# CONTROL_AND_COMMUNICATION.net
KiCad netlist of a schematic drawn in Altium Designer
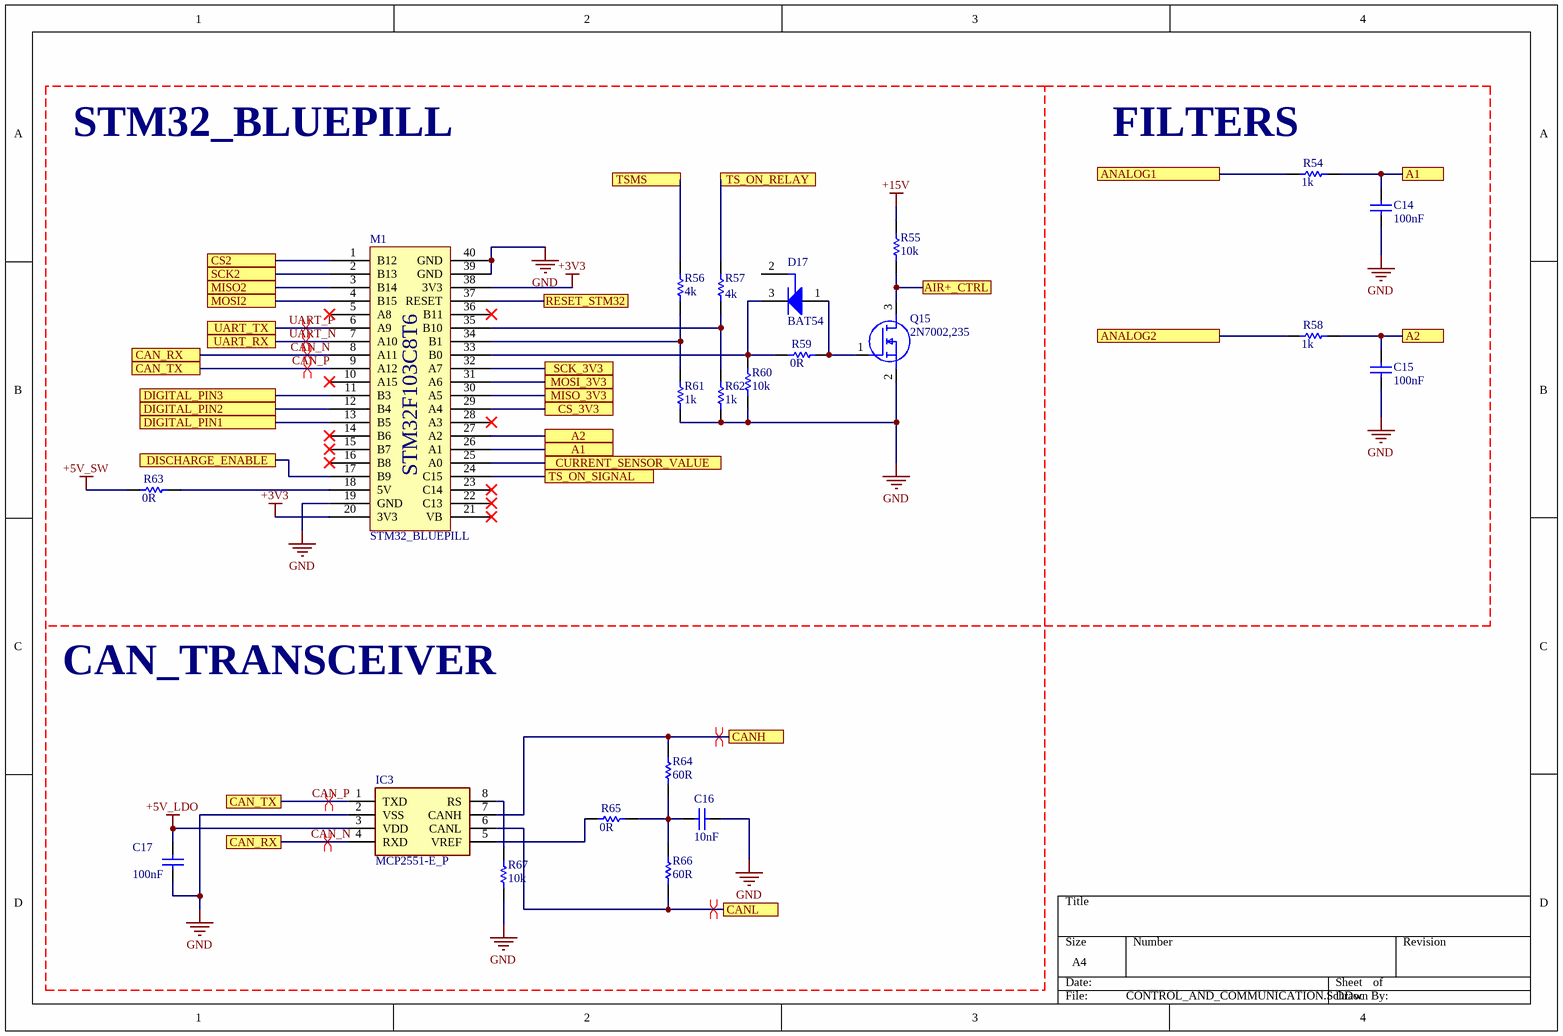
[diagram p0: CONTROL_AND_COMMUNICATION.SchDoc]

(export (version "E")
  (design (tool "Eeschema 10.0.6"))
  (components
    (comp (ref "C14")
      (value "100nF")
      (footprint "KEMT-1206-2_N")
      (description "CAP, Ceramic, 0.1 uF, +/- 10%, 50 V, -55 to 125 degC, 1206 (3216 Metric), RoHS, Tape and Reel")
      (fields (field (name "MANUFACTURER") "Kemet"))
      (libsource (lib "Schlib1_TSAL_LV_3.1") (part "CMP-1037-04202-2"))
    )
    (comp (ref "C15")
      (value "100nF")
      (footprint "KEMT-1206-2_N")
      (description "CAP, Ceramic, 0.1 uF, +/- 10%, 50 V, -55 to 125 degC, 1206 (3216 Metric), RoHS, Tape and Reel")
      (fields (field (name "MANUFACTURER") "Kemet"))
      (libsource (lib "Schlib1_TSAL_LV_3.1") (part "CMP-1037-04202-2"))
    )
    (comp (ref "C16")
      (value "10nF")
      (footprint "KEMT-1206-2_N")
      (description "CAP, Ceramic, 0.1 uF, +/- 10%, 50 V, -55 to 125 degC, 1206 (3216 Metric), RoHS, Tape and Reel")
      (fields (field (name "MANUFACTURER") "Kemet"))
      (libsource (lib "Schlib1_TSAL_LV_3.1") (part "CMP-1037-04202-2"))
    )
    (comp (ref "C17")
      (value "100nF")
      (footprint "KEMT-1206-2_N")
      (description "CAP, Ceramic, 0.1 uF, +/- 10%, 50 V, -55 to 125 degC, 1206 (3216 Metric), RoHS, Tape and Reel")
      (fields (field (name "MANUFACTURER") "Kemet"))
      (libsource (lib "Schlib1_TSAL_LV_3.1") (part "CMP-1037-04202-2"))
    )
    (comp (ref "D17")
      (value "BAT54")
      (footprint "INF-SOT23_N")
      (description "Silicon Schottky Diode, SOT23, Reel, Green")
      (fields (field (name "MANUFACTURER") "Infineon"))
      (libsource (lib "Schlib1") (part "CMP-1182-00010-1"))
    )
    (comp (ref "IC3")
      (value "MCP2551-E_P")
      (footprint "SamacSys:DIP794W56P254L946H432Q8N")
      (description "Integrated Circuit")
      (fields
        (field (name "MANUFACTURER_PART_NUMBER") "MCP2551-E/P")
        (field (name "MOUSER PART NUMBER") "579-MCP2551-E/P")
      )
      (libsource (lib "*") (part "MCP2551-E_P"))
    )
    (comp (ref "M1")
      (value "STM32_BLUEPILL")
      (footprint "stm32_bluepill")
      (libsource (lib "Regular_used_components_2D_Symbol") (part "stm32_bluepill"))
    )
    (comp (ref "Q15")
      (value "2N7002,235")
      (footprint "SamacSys:SOT95P230X110-3N")
      (description "MOSFET (N-Channel)")
      (fields (field (name "MOUSER PART NUMBER") "771-2N7002235"))
      (libsource (lib "*") (part "2N7002,235"))
    )
    (comp (ref "R54")
      (value "1k")
      (footprint "RESC3216X60X45NL10T20 - duplicate")
      (fields (field (name "PART NUMBER") "CRCW120647K0FKEA") (field (name "MANUFACTURER") "Vishay Dale"))
      (libsource (lib "Regular_used_components_2D_Symbol") (part "CMP-2003-02213-1"))
    )
    (comp (ref "R55")
      (value "10k")
      (footprint "RESC3216X60X45NL10T20 - duplicate")
      (fields (field (name "PART NUMBER") "CRCW120647K0FKEA") (field (name "MANUFACTURER") "Vishay Dale"))
      (libsource (lib "Regular_used_components_2D_Symbol") (part "CMP-2003-02213-1"))
    )
    (comp (ref "R56")
      (value "4k")
      (footprint "RESC3216X60X45NL10T20 - duplicate")
      (fields (field (name "PART NUMBER") "CRCW120647K0FKEA") (field (name "MANUFACTURER") "Vishay Dale"))
      (libsource (lib "Regular_used_components_2D_Symbol") (part "CMP-2003-02213-1"))
    )
    (comp (ref "R57")
      (value "4k")
      (footprint "RESC3216X60X45NL10T20 - duplicate")
      (fields (field (name "PART NUMBER") "CRCW120647K0FKEA") (field (name "MANUFACTURER") "Vishay Dale"))
      (libsource (lib "Regular_used_components_2D_Symbol") (part "CMP-2003-02213-1"))
    )
    (comp (ref "R58")
      (value "1k")
      (footprint "RESC3216X60X45NL10T20 - duplicate")
      (fields (field (name "PART NUMBER") "CRCW120647K0FKEA") (field (name "MANUFACTURER") "Vishay Dale"))
      (libsource (lib "Regular_used_components_2D_Symbol") (part "CMP-2003-02213-1"))
    )
    (comp (ref "R59")
      (value "0R")
      (footprint "RESC3216X60X45NL10T20 - duplicate")
      (fields (field (name "PART NUMBER") "CRCW120647K0FKEA") (field (name "MANUFACTURER") "Vishay Dale"))
      (libsource (lib "Regular_used_components_2D_Symbol") (part "CMP-2003-02213-1"))
    )
    (comp (ref "R60")
      (value "10k")
      (footprint "RESC3216X60X45NL10T20 - duplicate")
      (fields (field (name "PART NUMBER") "CRCW120647K0FKEA") (field (name "MANUFACTURER") "Vishay Dale"))
      (libsource (lib "Regular_used_components_2D_Symbol") (part "CMP-2003-02213-1"))
    )
    (comp (ref "R61")
      (value "1k")
      (footprint "RESC3216X60X45NL10T20 - duplicate")
      (fields (field (name "PART NUMBER") "CRCW120647K0FKEA") (field (name "MANUFACTURER") "Vishay Dale"))
      (libsource (lib "Regular_used_components_2D_Symbol") (part "CMP-2003-02213-1"))
    )
    (comp (ref "R62")
      (value "1k")
      (footprint "RESC3216X60X45NL10T20 - duplicate")
      (fields (field (name "PART NUMBER") "CRCW120647K0FKEA") (field (name "MANUFACTURER") "Vishay Dale"))
      (libsource (lib "Regular_used_components_2D_Symbol") (part "CMP-2003-02213-1"))
    )
    (comp (ref "R63")
      (value "0R")
      (footprint "RESC3216X60X45NL10T20 - duplicate")
      (fields (field (name "PART NUMBER") "CRCW120647K0FKEA") (field (name "MANUFACTURER") "Vishay Dale"))
      (libsource (lib "Regular_used_components_2D_Symbol") (part "CMP-2003-02213-1"))
    )
    (comp (ref "R64")
      (value "60R")
      (footprint "RESC3216X60X45NL10T20 - duplicate")
      (fields (field (name "PART NUMBER") "CRCW120647K0FKEA") (field (name "MANUFACTURER") "Vishay Dale"))
      (libsource (lib "Regular_used_components_2D_Symbol") (part "CMP-2003-02213-1"))
    )
    (comp (ref "R65")
      (value "0R")
      (footprint "RESC3216X60X45NL10T20 - duplicate")
      (fields (field (name "PART NUMBER") "CRCW120647K0FKEA") (field (name "MANUFACTURER") "Vishay Dale"))
      (libsource (lib "Regular_used_components_2D_Symbol") (part "CMP-2003-02213-1"))
    )
    (comp (ref "R66")
      (value "60R")
      (footprint "RESC3216X60X45NL10T20 - duplicate")
      (fields (field (name "PART NUMBER") "CRCW120647K0FKEA") (field (name "MANUFACTURER") "Vishay Dale"))
      (libsource (lib "Regular_used_components_2D_Symbol") (part "CMP-2003-02213-1"))
    )
    (comp (ref "R67")
      (value "10k")
      (footprint "RESC3216X60X45NL10T20 - duplicate")
      (fields (field (name "PART NUMBER") "CRCW120647K0FKEA") (field (name "MANUFACTURER") "Vishay Dale"))
      (libsource (lib "Regular_used_components_2D_Symbol") (part "CMP-2003-02213-1"))
    )
  )
  (nets
    (net (code "1") (name "+3V3") (class "Default")
      (node (ref "M1") (pin "20") (pinfunction "3V3_20") (pintype "passive"))
      (node (ref "M1") (pin "38") (pinfunction "3V3_38") (pintype "passive"))
    )
    (net (code "2") (name "+5V_LDO") (class "Default")
      (node (ref "C17") (pin "1") (pinfunction "1_1") (pintype "passive"))
      (node (ref "IC3") (pin "3") (pinfunction "VDD_3") (pintype "passive"))
    )
    (net (code "3") (name "+5V_SW") (class "Default")
      (node (ref "R63") (pin "2") (pinfunction "2_2") (pintype "passive"))
    )
    (net (code "4") (name "+15V") (class "Default")
      (node (ref "R55") (pin "1") (pinfunction "1_1") (pintype "passive"))
    )
    (net (code "5") (name "/A1") (class "Default")
      (node (ref "C14") (pin "1") (pinfunction "1_1") (pintype "passive"))
      (node (ref "M1") (pin "26") (pinfunction "A1_26") (pintype "passive"))
      (node (ref "R54") (pin "1") (pinfunction "1_1") (pintype "passive"))
    )
    (net (code "6") (name "/A2") (class "Default")
      (node (ref "C15") (pin "1") (pinfunction "1_1") (pintype "passive"))
      (node (ref "M1") (pin "27") (pinfunction "A2_27") (pintype "passive"))
      (node (ref "R58") (pin "1") (pinfunction "1_1") (pintype "passive"))
    )
    (net (code "7") (name "/AIR+_CTRL") (class "Default")
      (node (ref "Q15") (pin "3") (pinfunction "D_3") (pintype "passive"))
      (node (ref "R55") (pin "2") (pinfunction "2_2") (pintype "passive"))
    )
    (net (code "8") (name "/ANALOG1") (class "Default")
      (node (ref "R54") (pin "2") (pinfunction "2_2") (pintype "passive"))
    )
    (net (code "9") (name "/ANALOG2") (class "Default")
      (node (ref "R58") (pin "2") (pinfunction "2_2") (pintype "passive"))
    )
    (net (code "10") (name "/CANH") (class "Default")
      (node (ref "IC3") (pin "7") (pinfunction "CANH_7") (pintype "passive"))
      (node (ref "R64") (pin "2") (pinfunction "2_2") (pintype "passive"))
    )
    (net (code "11") (name "/CANL") (class "Default")
      (node (ref "IC3") (pin "6") (pinfunction "CANL_6") (pintype "passive"))
      (node (ref "R66") (pin "2") (pinfunction "2_2") (pintype "passive"))
    )
    (net (code "12") (name "/CAN_N") (class "Default")
      (node (ref "IC3") (pin "4") (pinfunction "RXD_4") (pintype "passive"))
      (node (ref "M1") (pin "8") (pinfunction "A11_8") (pintype "passive"))
    )
    (net (code "13") (name "/CAN_P") (class "Default")
      (node (ref "IC3") (pin "1") (pinfunction "TXD_1") (pintype "passive"))
      (node (ref "M1") (pin "9") (pinfunction "A12_9") (pintype "passive"))
    )
    (net (code "14") (name "/CS2") (class "Default")
      (node (ref "M1") (pin "1") (pinfunction "B12_1") (pintype "passive"))
    )
    (net (code "15") (name "/CS_3V3") (class "Default")
      (node (ref "M1") (pin "29") (pinfunction "A4_29") (pintype "passive"))
    )
    (net (code "16") (name "/CURRENT_SENSOR_VALUE") (class "Default")
      (node (ref "M1") (pin "25") (pinfunction "A0_25") (pintype "passive"))
    )
    (net (code "17") (name "/DIGITAL_PIN1") (class "Default")
      (node (ref "M1") (pin "13") (pinfunction "B5_13") (pintype "passive"))
    )
    (net (code "18") (name "/DIGITAL_PIN2") (class "Default")
      (node (ref "M1") (pin "12") (pinfunction "B4_12") (pintype "passive"))
    )
    (net (code "19") (name "/DIGITAL_PIN3") (class "Default")
      (node (ref "M1") (pin "11") (pinfunction "B3_11") (pintype "passive"))
    )
    (net (code "20") (name "/DISCHARGE_ENABLE") (class "Default")
      (node (ref "M1") (pin "17") (pinfunction "B9_17") (pintype "passive"))
    )
    (net (code "21") (name "/MISO2") (class "Default")
      (node (ref "M1") (pin "3") (pinfunction "B14_3") (pintype "passive"))
    )
    (net (code "22") (name "/MISO_3V3") (class "Default")
      (node (ref "M1") (pin "30") (pinfunction "A5_30") (pintype "passive"))
    )
    (net (code "23") (name "/MOSI2") (class "Default")
      (node (ref "M1") (pin "4") (pinfunction "B15_4") (pintype "passive"))
    )
    (net (code "24") (name "/MOSI_3V3") (class "Default")
      (node (ref "M1") (pin "31") (pinfunction "A6_31") (pintype "passive"))
    )
    (net (code "25") (name "/RESET_STM32") (class "Default")
      (node (ref "M1") (pin "37") (pinfunction "RESET_37") (pintype "passive"))
    )
    (net (code "26") (name "/SCK2") (class "Default")
      (node (ref "M1") (pin "2") (pinfunction "B13_2") (pintype "passive"))
    )
    (net (code "27") (name "/SCK_3V3") (class "Default")
      (node (ref "M1") (pin "32") (pinfunction "A7_32") (pintype "passive"))
    )
    (net (code "28") (name "/TSMS") (class "Default")
      (node (ref "R56") (pin "1") (pinfunction "1_1") (pintype "passive"))
    )
    (net (code "29") (name "/TS_ON_RELAY") (class "Default")
      (node (ref "R57") (pin "1") (pinfunction "1_1") (pintype "passive"))
    )
    (net (code "30") (name "/TS_ON_SIGNAL") (class "Default")
      (node (ref "M1") (pin "24") (pinfunction "C15_24") (pintype "passive"))
    )
    (net (code "31") (name "/UART_N") (class "Default")
      (node (ref "M1") (pin "7") (pinfunction "A10_7") (pintype "passive"))
    )
    (net (code "32") (name "/UART_P") (class "Default")
      (node (ref "M1") (pin "6") (pinfunction "A9_6") (pintype "passive"))
    )
    (net (code "33") (name "GND") (class "Default")
      (node (ref "C14") (pin "2") (pinfunction "2_2") (pintype "passive"))
      (node (ref "C15") (pin "2") (pinfunction "2_2") (pintype "passive"))
      (node (ref "C16") (pin "2") (pinfunction "2_2") (pintype "passive"))
      (node (ref "C17") (pin "2") (pinfunction "2_2") (pintype "passive"))
      (node (ref "IC3") (pin "2") (pinfunction "VSS_2") (pintype "passive"))
      (node (ref "M1") (pin "19") (pinfunction "GND_19") (pintype "passive"))
      (node (ref "M1") (pin "39") (pinfunction "GND_39") (pintype "passive"))
      (node (ref "M1") (pin "40") (pinfunction "GND_40") (pintype "passive"))
      (node (ref "Q15") (pin "2") (pinfunction "S_2") (pintype "passive"))
      (node (ref "R60") (pin "2") (pinfunction "2_2") (pintype "passive"))
      (node (ref "R61") (pin "2") (pinfunction "2_2") (pintype "passive"))
      (node (ref "R62") (pin "2") (pinfunction "2_2") (pintype "passive"))
      (node (ref "R67") (pin "2") (pinfunction "2_2") (pintype "passive"))
    )
    (net (code "34") (name "Net-(C16-Pad1)") (class "Default")
      (node (ref "C16") (pin "1") (pinfunction "1_1") (pintype "passive"))
      (node (ref "R64") (pin "1") (pinfunction "1_1") (pintype "passive"))
      (node (ref "R65") (pin "1") (pinfunction "1_1") (pintype "passive"))
      (node (ref "R66") (pin "1") (pinfunction "1_1") (pintype "passive"))
    )
    (net (code "35") (name "Net-(D17-A)") (class "Default")
      (node (ref "D17") (pin "1") (pinfunction "A_1") (pintype "passive"))
      (node (ref "Q15") (pin "1") (pinfunction "G_1") (pintype "passive"))
      (node (ref "R59") (pin "1") (pinfunction "1_1") (pintype "passive"))
    )
    (net (code "36") (name "Net-(D17-K)") (class "Default")
      (node (ref "D17") (pin "3") (pinfunction "K_3") (pintype "passive"))
      (node (ref "M1") (pin "33") (pinfunction "B0_33") (pintype "passive"))
      (node (ref "R59") (pin "2") (pinfunction "2_2") (pintype "passive"))
      (node (ref "R60") (pin "1") (pinfunction "1_1") (pintype "passive"))
    )
    (net (code "37") (name "Net-(IC3-RS)") (class "Default")
      (node (ref "IC3") (pin "8") (pinfunction "RS_8") (pintype "passive"))
      (node (ref "R67") (pin "1") (pinfunction "1_1") (pintype "passive"))
    )
    (net (code "38") (name "Net-(IC3-VREF)") (class "Default")
      (node (ref "IC3") (pin "5") (pinfunction "VREF_5") (pintype "passive"))
      (node (ref "R65") (pin "2") (pinfunction "2_2") (pintype "passive"))
    )
    (net (code "39") (name "Net-(M1-5V)") (class "Default")
      (node (ref "M1") (pin "18") (pinfunction "5V_18") (pintype "passive"))
      (node (ref "R63") (pin "1") (pinfunction "1_1") (pintype "passive"))
    )
    (net (code "40") (name "Net-(M1-B1)") (class "Default")
      (node (ref "M1") (pin "34") (pinfunction "B1_34") (pintype "passive"))
      (node (ref "R56") (pin "2") (pinfunction "2_2") (pintype "passive"))
      (node (ref "R61") (pin "1") (pinfunction "1_1") (pintype "passive"))
    )
    (net (code "41") (name "Net-(M1-B10)") (class "Default")
      (node (ref "M1") (pin "35") (pinfunction "B10_35") (pintype "passive"))
      (node (ref "R57") (pin "2") (pinfunction "2_2") (pintype "passive"))
      (node (ref "R62") (pin "1") (pinfunction "1_1") (pintype "passive"))
    )
    (net (code "42") (name "unconnected-(D17-NC-Pad2)") (class "Default")
      (node (ref "D17") (pin "2") (pinfunction "NC_2") (pintype "passive"))
    )
    (net (code "43") (name "unconnected-(M1-A3-Pad28)") (class "Default")
      (node (ref "M1") (pin "28") (pinfunction "A3_28") (pintype "passive+no_connect"))
    )
    (net (code "44") (name "unconnected-(M1-A8-Pad5)") (class "Default")
      (node (ref "M1") (pin "5") (pinfunction "A8_5") (pintype "passive+no_connect"))
    )
    (net (code "45") (name "unconnected-(M1-A15-Pad10)") (class "Default")
      (node (ref "M1") (pin "10") (pinfunction "A15_10") (pintype "passive+no_connect"))
    )
    (net (code "46") (name "unconnected-(M1-B6-Pad14)") (class "Default")
      (node (ref "M1") (pin "14") (pinfunction "B6_14") (pintype "passive+no_connect"))
    )
    (net (code "47") (name "unconnected-(M1-B7-Pad15)") (class "Default")
      (node (ref "M1") (pin "15") (pinfunction "B7_15") (pintype "passive+no_connect"))
    )
    (net (code "48") (name "unconnected-(M1-B8-Pad16)") (class "Default")
      (node (ref "M1") (pin "16") (pinfunction "B8_16") (pintype "passive+no_connect"))
    )
    (net (code "49") (name "unconnected-(M1-B11-Pad36)") (class "Default")
      (node (ref "M1") (pin "36") (pinfunction "B11_36") (pintype "passive+no_connect"))
    )
    (net (code "50") (name "unconnected-(M1-C13-Pad22)") (class "Default")
      (node (ref "M1") (pin "22") (pinfunction "C13_22") (pintype "passive+no_connect"))
    )
    (net (code "51") (name "unconnected-(M1-C14-Pad23)") (class "Default")
      (node (ref "M1") (pin "23") (pinfunction "C14_23") (pintype "passive+no_connect"))
    )
    (net (code "52") (name "unconnected-(M1-VB-Pad21)") (class "Default")
      (node (ref "M1") (pin "21") (pinfunction "VB_21") (pintype "passive+no_connect"))
    )
  )
)
